# OUTPUT_RELAY.net
KiCad netlist of a schematic drawn in Altium Designer
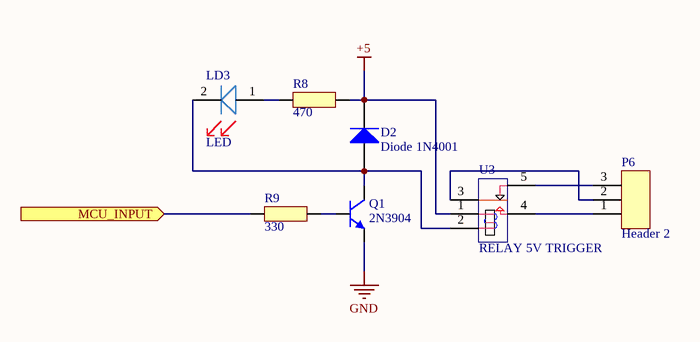
[diagram p0: OUTPUT_RELAY.SchDoc]

(export (version "E")
  (design (tool "Eeschema 10.0.6"))
  (components
    (comp (ref "D2")
      (value "Diode 1N4001")
      (footprint "DO-41")
      (description "1 Amp General Purpose Rectifier")
      (fields (field (name "PUBLISHER") "Altium Limited"))
      (libsource (lib "Miscellaneous Devices") (part "Diode 1N4001"))
    )
    (comp (ref "LD3")
      (value "LED")
      (footprint "LED_SMD")
      (description "0805")
      (fields (field (name "PUBLISHER") "Altium Limited"))
      (libsource (lib "TOAN_ONG_Library") (part "LED_SMD"))
    )
    (comp (ref "P6")
      (value "Header 2")
      (footprint "3 PIN TERMINAL")
      (description "Header, 2-Pin")
      (fields (field (name "PUBLISHER") "Altium Limited"))
      (libsource (lib "TOAN_ONG_Library") (part "3 PIN TERMINAL"))
    )
    (comp (ref "Q1")
      (value "2N3904")
      (footprint "SOT23C")
      (description "NPN General Purpose Amplifier")
      (fields (field (name "PUBLISHER") "Altium Limited"))
      (libsource (lib "kidteam_ad_SCH") (part "2N3904"))
    )
    (comp (ref "R8")
      (value "470")
      (footprint "Resistor")
      (description "Resistor")
      (fields (field (name "PUBLISHER") "Altium Limited"))
      (libsource (lib "TOAN_ONG_Library") (part "Resistor"))
    )
    (comp (ref "R9")
      (value "330")
      (footprint "Resistor")
      (description "Resistor")
      (fields (field (name "PUBLISHER") "Altium Limited"))
      (libsource (lib "") (part "Resistor_1"))
    )
    (comp (ref "U3")
      (value "RELAY 5V TRIGGER")
      (footprint "RELAY 5V TRIGGER")
      (description "Header, 2-Pin")
      (fields (field (name "PUBLISHER") "Altium Limited"))
      (libsource (lib "TOAN_ONG_Library") (part "RELAY 5V TRIGGER"))
    )
  )
  (nets
    (net (code "1") (name "+5") (class "Default")
      (node (ref "D2") (pin "2") (pinfunction "K_2") (pintype "passive"))
      (node (ref "R8") (pin "1") (pinfunction "1_1") (pintype "passive"))
      (node (ref "U3") (pin "1") (pinfunction "1_1") (pintype "passive"))
    )
    (net (code "2") (name "/MCU_INPUT") (class "Default")
      (node (ref "R9") (pin "1") (pinfunction "1_1") (pintype "passive"))
    )
    (net (code "3") (name "GND") (class "Default")
      (node (ref "Q1") (pin "1") (pinfunction "E_1") (pintype "passive"))
    )
    (net (code "4") (name "Net-(D2-A)") (class "Default")
      (node (ref "D2") (pin "1") (pinfunction "A_1") (pintype "passive"))
      (node (ref "LD3") (pin "2") (pinfunction "2_2") (pintype "passive"))
      (node (ref "Q1") (pin "3") (pinfunction "C_3") (pintype "passive"))
      (node (ref "U3") (pin "2") (pinfunction "2_2") (pintype "passive"))
    )
    (net (code "5") (name "Net-(LD3-Pad1)") (class "Default")
      (node (ref "LD3") (pin "1") (pinfunction "1_1") (pintype "passive"))
      (node (ref "R8") (pin "2") (pinfunction "2_2") (pintype "passive"))
    )
    (net (code "6") (name "Net-(P6-Pad1)") (class "Default")
      (node (ref "P6") (pin "1") (pinfunction "1_1") (pintype "passive"))
      (node (ref "U3") (pin "4") (pinfunction "4_4") (pintype "passive"))
    )
    (net (code "7") (name "Net-(P6-Pad2)") (class "Default")
      (node (ref "P6") (pin "2") (pinfunction "2_2") (pintype "passive"))
      (node (ref "U3") (pin "3") (pinfunction "3_3") (pintype "passive"))
    )
    (net (code "8") (name "Net-(P6-Pad3)") (class "Default")
      (node (ref "P6") (pin "3") (pinfunction "3_3") (pintype "passive"))
      (node (ref "U3") (pin "5") (pinfunction "5_5") (pintype "passive"))
    )
    (net (code "9") (name "Net-(Q1-B)") (class "Default")
      (node (ref "Q1") (pin "2") (pinfunction "B_2") (pintype "passive"))
      (node (ref "R9") (pin "2") (pinfunction "2_2") (pintype "passive"))
    )
  )
)
